# Sensors.net
KiCad netlist of a schematic drawn in Altium Designer
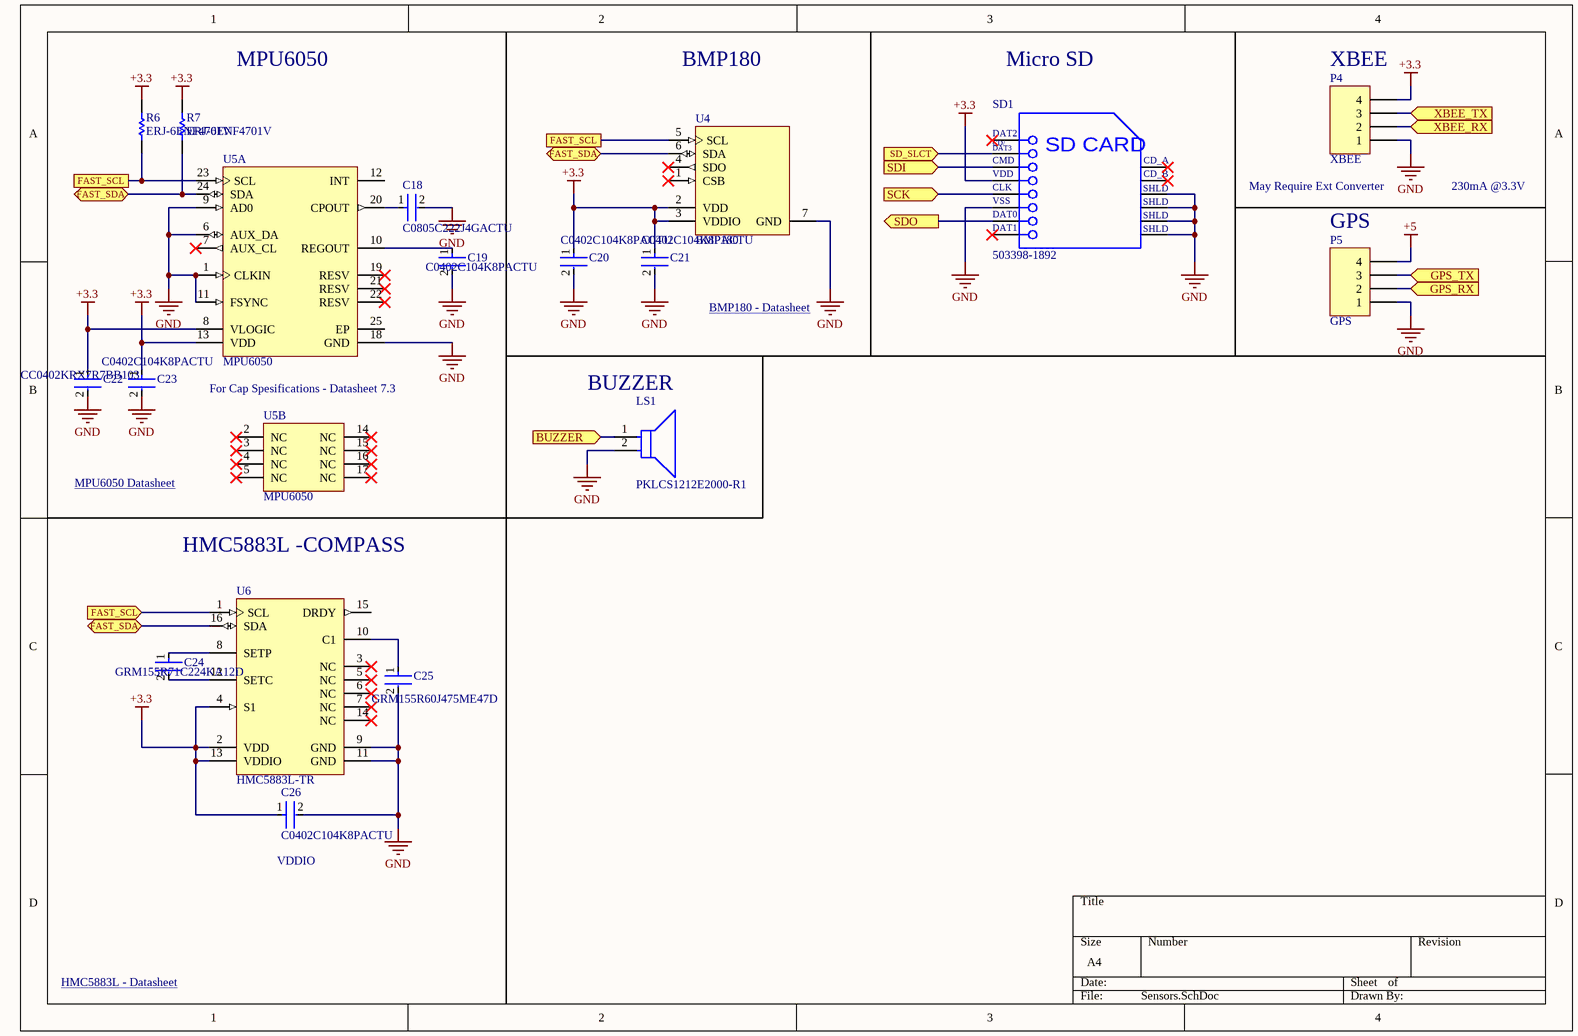
[diagram p0: Sensors.SchDoc]

(export (version "E")
  (design (tool "Eeschema 10.0.6"))
  (components
    (comp (ref "C18")
      (value "C0805C222J4GACTU")
      (footprint "FP-C0805C-DN-MFG")
      (description "Capacitor, Ceramic, 2.2Nf, 16Vdc, 5-% Tol, 5+% Tol, C0g-Tc Code, -30, 30Ppm-Tc Rohs Compliant: Yes")
      (fields
        (field (name "OCTOPART") "https://octopart.com/c0805c222j4gactu-kemet-17052493")
        (field (name "MANUFACTURER") "KEMET")
      )
      (libsource (lib "Altium Content Vault") (part "b4654b650e69147ec39a6b967a45e02"))
    )
    (comp (ref "C19")
      (value "C0402C104K8PACTU")
      (footprint "FP-C0402-BB-MFG")
      (description "CAP CER 0.1UF 10V X5R 0402")
      (fields (field (name "MANUFACTURER") "Kemet") (field (name "TOLERANCE") "0.1"))
      (libsource (lib "Altium Content Vault") (part "b4654b650e69147ec39a6b967a45e02"))
    )
    (comp (ref "C20")
      (value "C0402C104K8PACTU")
      (footprint "FP-C0402-BB-MFG")
      (description "CAP CER 0.1UF 10V X5R 0402")
      (fields (field (name "MANUFACTURER") "Kemet") (field (name "TOLERANCE") "0.1"))
      (libsource (lib "Altium Content Vault") (part "b4654b650e69147ec39a6b967a45e02"))
    )
    (comp (ref "C21")
      (value "C0402C104K8PACTU")
      (footprint "FP-C0402-BB-MFG")
      (description "CAP CER 0.1UF 10V X5R 0402")
      (fields (field (name "MANUFACTURER") "Kemet") (field (name "TOLERANCE") "0.1"))
      (libsource (lib "Altium Content Vault") (part "b4654b650e69147ec39a6b967a45e02"))
    )
    (comp (ref "C22")
      (value "CC0402KRX7R7BB103")
      (footprint "FP-CC0402-MFG")
      (description "CAP CER 10000PF 16V X7R 0402")
      (fields (field (name "TOLERANCE") "0.1") (field (name "MANUFACTURER") "YAGEO"))
      (libsource (lib "Altium Content Vault") (part "11868f565c42a9108669ba33697ecf6"))
    )
    (comp (ref "C23")
      (value "C0402C104K8PACTU")
      (footprint "FP-C0402-BB-MFG")
      (description "CAP CER 0.1UF 10V X5R 0402")
      (fields (field (name "MANUFACTURER") "Kemet") (field (name "TOLERANCE") "0.1"))
      (libsource (lib "Altium Content Vault") (part "b4654b650e69147ec39a6b967a45e02"))
    )
    (comp (ref "C24")
      (value "GRM155R71C224KA12D")
      (footprint "FP-GRM155-0_05-IPC_C")
      (description "Chip Multilayer Ceramic Capacitors for General Purpose, 0402, 0.22uF, X7R, 15%, 10%, 16V")
      (fields (field (name "VOLTAGE") "16V") (field (name "TOLERANCE") "10%"))
      (libsource (lib "Altium Content Vault") (part "02cd4be3c70576c341d710602a673aa"))
    )
    (comp (ref "C25")
      (value "GRM155R60J475ME47D")
      (footprint "FP-GRM155-0_1-IPC_B")
      (description "Chip Multilayer Ceramic Capacitors for General Purpose, 0402, 4.7uF, X5R, 15%, 20%, 6.3V")
      (fields (field (name "VOLTAGE") "6.3V") (field (name "TOLERANCE") "20%"))
      (libsource (lib "Altium Content Vault") (part "11868f565c42a9108669ba33697ecf6"))
    )
    (comp (ref "C26")
      (value "C0402C104K8PACTU")
      (footprint "FP-C0402-BB-MFG")
      (description "CAP CER 0.1UF 10V X5R 0402")
      (fields (field (name "MANUFACTURER") "Kemet") (field (name "TOLERANCE") "0.1"))
      (libsource (lib "Altium Content Vault") (part "b4654b650e69147ec39a6b967a45e02"))
    )
    (comp (ref "LS1")
      (value "PKLCS1212E2000-R1")
      (footprint "FP-PKLCS1212E2000-R1-MFG")
      (description "AUDIO PIEZO TRANSDUCER 12.5V SMD")
      (fields
        (field (name "MANUFACTURER") "Murata")
        (field (name "OCTOPART") "https://octopart.com/pklcs1212e2000-r1-murata-7123179")
      )
      (libsource (lib "Altium Content Vault") (part "5f581d31613f872430949aa526fd155"))
    )
    (comp (ref "P4")
      (value "XBEE")
      (footprint "HDR1X4")
      (description "Header, 4-Pin")
      (fields (field (name "PUBLISHER") "Altium Limited"))
      (libsource (lib "Miscellaneous Connectors") (part "Header 4"))
    )
    (comp (ref "P5")
      (value "GPS")
      (footprint "HDR1X4")
      (description "Header, 4-Pin")
      (fields (field (name "PUBLISHER") "Altium Limited"))
      (libsource (lib "Miscellaneous Connectors") (part "Header 4"))
    )
    (comp (ref "R6")
      (value "ERJ-6ENF4701V")
      (footprint "RESC2013X70X40NL20T20")
      (description "Chip Resistor, 4.7 KOhm, +/- 1%, 0.125 W, -55 to 155 degC, 0805 (2012 Metric), RoHS, Tape and Reel")
      (fields (field (name "MANUFACTURER") "Panasonic"))
      (libsource (lib "Altium Content Vault") (part "RES-2"))
    )
    (comp (ref "R7")
      (value "ERJ-6ENF4701V")
      (footprint "RESC2013X70X40NL20T20")
      (description "Chip Resistor, 4.7 KOhm, +/- 1%, 0.125 W, -55 to 155 degC, 0805 (2012 Metric), RoHS, Tape and Reel")
      (fields (field (name "MANUFACTURER") "Panasonic"))
      (libsource (lib "Altium Content Vault") (part "RES-2"))
    )
    (comp (ref "SD1")
      (value "503398-1892")
      (footprint "MOLX-503398-1892_V")
      (description "Micro SD Connector, Pitch 1.1 mm, 8 Position, Height 1.4 mm, -25 to 85 degC, RoHS, Tape and Reel")
      (fields (field (name "MANUFACTURER") "Molex"))
      (libsource (lib "Altium Content Vault") (part "CN-SD-8-2SW-4S"))
    )
    (comp (ref "U4")
      (value "BMP180")
      (footprint "BOSC-BMP180-7_V")
      (description "Digital Pressure Sensor, 1.8 to 3.6 V, -40 to 85 degC, 7-Pin LGA, RoHS")
      (fields (field (name "MANUFACTURER") "Bosch Sensortec"))
      (libsource (lib "Altium Content Vault") (part "BOSC-BMP180-7"))
    )
    (comp (ref "U5")
      (value "MPU6050")
      (footprint "INSE-QFN-24_V")
      (fields (field (name "TOLERANCE") "1%"))
      (libsource (lib "Altium Content Vault") (part "INSE-MPU6050-QFN-24"))
    )
    (comp (ref "U6")
      (value "HMC5883L-TR")
      (footprint "HONEY-LPCC-16_V")
      (description "Three-Axis Digital Compass IC, 2.16 to 3.6 V, -30 to 85 degC, 16-Pin PLCC, RoHS, Tape and Reel")
      (fields (field (name "MANUFACTURER") "Honeywell"))
      (libsource (lib "Altium Content Vault") (part "HONEY-HMC5883L-TR-LPCC-16"))
    )
  )
  (nets
    (net (code "1") (name "+3.3") (class "Default")
      (node (ref "C20") (pin "1") (pinfunction "1_1") (pintype "passive"))
      (node (ref "C21") (pin "1") (pinfunction "1_1") (pintype "passive"))
      (node (ref "C22") (pin "1") (pinfunction "1_1") (pintype "passive"))
      (node (ref "C23") (pin "1") (pinfunction "1_1") (pintype "passive"))
      (node (ref "C26") (pin "1") (pinfunction "1_1") (pintype "passive"))
      (node (ref "P4") (pin "4") (pinfunction "4_4") (pintype "passive"))
      (node (ref "R6") (pin "2") (pinfunction "2_2") (pintype "passive"))
      (node (ref "R7") (pin "2") (pinfunction "2_2") (pintype "passive"))
      (node (ref "SD1") (pin "4") (pinfunction "VDD_4") (pintype "passive"))
      (node (ref "U4") (pin "2") (pinfunction "VDD_2") (pintype "power_in"))
      (node (ref "U4") (pin "3") (pinfunction "VDDIO_3") (pintype "power_in"))
      (node (ref "U5") (pin "13") (pinfunction "VDD_13") (pintype "power_in"))
      (node (ref "U5") (pin "8") (pinfunction "VLOGIC_8") (pintype "power_in"))
      (node (ref "U6") (pin "13") (pinfunction "VDDIO_13") (pintype "power_in"))
      (node (ref "U6") (pin "2") (pinfunction "VDD_2") (pintype "power_in"))
      (node (ref "U6") (pin "4") (pinfunction "S1_4") (pintype "input"))
    )
    (net (code "2") (name "+5") (class "Default")
      (node (ref "P5") (pin "4") (pinfunction "4_4") (pintype "passive"))
    )
    (net (code "3") (name "/BUZZER") (class "Default")
      (node (ref "LS1") (pin "1") (pinfunction "1_1") (pintype "passive"))
    )
    (net (code "4") (name "/FAST_SCL") (class "Default")
      (node (ref "R6") (pin "1") (pinfunction "1_1") (pintype "passive"))
      (node (ref "U4") (pin "5") (pinfunction "SCL_5") (pintype "input"))
      (node (ref "U5") (pin "23") (pinfunction "SCL_23") (pintype "input"))
      (node (ref "U6") (pin "1") (pinfunction "SCL_1") (pintype "input"))
    )
    (net (code "5") (name "/FAST_SDA") (class "Default")
      (node (ref "R7") (pin "1") (pinfunction "1_1") (pintype "passive"))
      (node (ref "U4") (pin "6") (pinfunction "SDA_6") (pintype "bidirectional"))
      (node (ref "U5") (pin "24") (pinfunction "SDA_24") (pintype "bidirectional"))
      (node (ref "U6") (pin "16") (pinfunction "SDA_16") (pintype "bidirectional"))
    )
    (net (code "6") (name "/GPS_RX") (class "Default")
      (node (ref "P5") (pin "2") (pinfunction "2_2") (pintype "passive"))
    )
    (net (code "7") (name "/GPS_TX") (class "Default")
      (node (ref "P5") (pin "3") (pinfunction "3_3") (pintype "passive"))
    )
    (net (code "8") (name "/SCK") (class "Default")
      (node (ref "SD1") (pin "5") (pinfunction "CLK_5") (pintype "passive"))
    )
    (net (code "9") (name "/SDI") (class "Default")
      (node (ref "SD1") (pin "3") (pinfunction "CMD_3") (pintype "passive"))
    )
    (net (code "10") (name "/SDO") (class "Default")
      (node (ref "SD1") (pin "7") (pinfunction "DAT0_7") (pintype "passive"))
    )
    (net (code "11") (name "/SD_SLCT") (class "Default")
      (node (ref "SD1") (pin "2") (pinfunction "CD/DAT3_2") (pintype "passive"))
    )
    (net (code "12") (name "/XBEE_RX") (class "Default")
      (node (ref "P4") (pin "2") (pinfunction "2_2") (pintype "passive"))
    )
    (net (code "13") (name "/XBEE_TX") (class "Default")
      (node (ref "P4") (pin "3") (pinfunction "3_3") (pintype "passive"))
    )
    (net (code "14") (name "GND") (class "Default")
      (node (ref "C18") (pin "2") (pinfunction "2_2") (pintype "passive"))
      (node (ref "C19") (pin "2") (pinfunction "2_2") (pintype "passive"))
      (node (ref "C20") (pin "2") (pinfunction "2_2") (pintype "passive"))
      (node (ref "C21") (pin "2") (pinfunction "2_2") (pintype "passive"))
      (node (ref "C22") (pin "2") (pinfunction "2_2") (pintype "passive"))
      (node (ref "C23") (pin "2") (pinfunction "2_2") (pintype "passive"))
      (node (ref "C25") (pin "2") (pinfunction "2_2") (pintype "passive"))
      (node (ref "C26") (pin "2") (pinfunction "2_2") (pintype "passive"))
      (node (ref "LS1") (pin "2") (pinfunction "2_2") (pintype "passive"))
      (node (ref "P4") (pin "1") (pinfunction "1_1") (pintype "passive"))
      (node (ref "P5") (pin "1") (pinfunction "1_1") (pintype "passive"))
      (node (ref "SD1") (pin "11") (pinfunction "SHLD_11") (pintype "passive"))
      (node (ref "SD1") (pin "12") (pinfunction "SHLD_12") (pintype "passive"))
      (node (ref "SD1") (pin "13") (pinfunction "SHLD_13") (pintype "passive"))
      (node (ref "SD1") (pin "14") (pinfunction "SHLD_14") (pintype "passive"))
      (node (ref "SD1") (pin "6") (pinfunction "VSS_6") (pintype "passive"))
      (node (ref "U4") (pin "7") (pinfunction "GND_7") (pintype "power_in"))
      (node (ref "U5") (pin "1") (pinfunction "CLKIN_1") (pintype "input"))
      (node (ref "U5") (pin "11") (pinfunction "FSYNC_11") (pintype "input"))
      (node (ref "U5") (pin "18") (pinfunction "GND_18") (pintype "power_in"))
      (node (ref "U5") (pin "6") (pinfunction "AUX_DA_6") (pintype "bidirectional"))
      (node (ref "U5") (pin "9") (pinfunction "AD0_9") (pintype "input"))
      (node (ref "U6") (pin "11") (pinfunction "GND_11") (pintype "power_in"))
      (node (ref "U6") (pin "9") (pinfunction "GND_9") (pintype "power_in"))
    )
    (net (code "15") (name "Net-(U5A-CPOUT)") (class "Default")
      (node (ref "C18") (pin "1") (pinfunction "1_1") (pintype "passive"))
      (node (ref "U5") (pin "20") (pinfunction "CPOUT_20") (pintype "output"))
    )
    (net (code "16") (name "Net-(U5A-REGOUT)") (class "Default")
      (node (ref "C19") (pin "1") (pinfunction "1_1") (pintype "passive"))
      (node (ref "U5") (pin "10") (pinfunction "REGOUT_10") (pintype "passive"))
    )
    (net (code "17") (name "Net-(U6-C1)") (class "Default")
      (node (ref "C25") (pin "1") (pinfunction "1_1") (pintype "passive"))
      (node (ref "U6") (pin "10") (pinfunction "C1_10") (pintype "passive"))
    )
    (net (code "18") (name "Net-(U6-SETC)") (class "Default")
      (node (ref "C24") (pin "2") (pinfunction "2_2") (pintype "passive"))
      (node (ref "U6") (pin "12") (pinfunction "SETC_12") (pintype "passive"))
    )
    (net (code "19") (name "Net-(U6-SETP)") (class "Default")
      (node (ref "C24") (pin "1") (pinfunction "1_1") (pintype "passive"))
      (node (ref "U6") (pin "8") (pinfunction "SETP_8") (pintype "passive"))
    )
    (net (code "20") (name "unconnected-(SD1-CD_A-Pad9)") (class "Default")
      (node (ref "SD1") (pin "9") (pinfunction "CD_A_9") (pintype "passive+no_connect"))
    )
    (net (code "21") (name "unconnected-(SD1-CD_B-Pad10)") (class "Default")
      (node (ref "SD1") (pin "10") (pinfunction "CD_B_10") (pintype "passive+no_connect"))
    )
    (net (code "22") (name "unconnected-(SD1-DAT1-Pad8)") (class "Default")
      (node (ref "SD1") (pin "8") (pinfunction "DAT1_8") (pintype "passive+no_connect"))
    )
    (net (code "23") (name "unconnected-(SD1-DAT2-Pad1)") (class "Default")
      (node (ref "SD1") (pin "1") (pinfunction "DAT2_1") (pintype "passive+no_connect"))
    )
    (net (code "24") (name "unconnected-(U4-CSB-Pad1)") (class "Default")
      (node (ref "U4") (pin "1") (pinfunction "CSB_1") (pintype "input+no_connect"))
    )
    (net (code "25") (name "unconnected-(U4-SDO-Pad4)") (class "Default")
      (node (ref "U4") (pin "4") (pinfunction "SDO_4") (pintype "output+no_connect"))
    )
    (net (code "26") (name "unconnected-(U5A-AUX_CL-Pad7)") (class "Default")
      (node (ref "U5") (pin "7") (pinfunction "AUX_CL_7") (pintype "output+no_connect"))
    )
    (net (code "27") (name "unconnected-(U5A-EP-Pad25)") (class "Default")
      (node (ref "U5") (pin "25") (pinfunction "EP_25") (pintype "passive"))
    )
    (net (code "28") (name "unconnected-(U5A-INT-Pad12)") (class "Default")
      (node (ref "U5") (pin "12") (pinfunction "INT_12") (pintype "open_collector"))
    )
    (net (code "29") (name "unconnected-(U5A-RESV-Pad19)") (class "Default")
      (node (ref "U5") (pin "19") (pinfunction "RESV_19") (pintype "passive+no_connect"))
    )
    (net (code "30") (name "unconnected-(U5A-RESV-Pad21)") (class "Default")
      (node (ref "U5") (pin "21") (pinfunction "RESV_21") (pintype "passive+no_connect"))
    )
    (net (code "31") (name "unconnected-(U5A-RESV-Pad22)") (class "Default")
      (node (ref "U5") (pin "22") (pinfunction "RESV_22") (pintype "passive+no_connect"))
    )
    (net (code "32") (name "unconnected-(U5B-NC-Pad2)") (class "Default")
      (node (ref "U5") (pin "2") (pinfunction "NC_2") (pintype "passive+no_connect"))
    )
    (net (code "33") (name "unconnected-(U5B-NC-Pad3)") (class "Default")
      (node (ref "U5") (pin "3") (pinfunction "NC_3") (pintype "passive+no_connect"))
    )
    (net (code "34") (name "unconnected-(U5B-NC-Pad4)") (class "Default")
      (node (ref "U5") (pin "4") (pinfunction "NC_4") (pintype "passive+no_connect"))
    )
    (net (code "35") (name "unconnected-(U5B-NC-Pad5)") (class "Default")
      (node (ref "U5") (pin "5") (pinfunction "NC_5") (pintype "passive+no_connect"))
    )
    (net (code "36") (name "unconnected-(U5B-NC-Pad14)") (class "Default")
      (node (ref "U5") (pin "14") (pinfunction "NC_14") (pintype "passive+no_connect"))
    )
    (net (code "37") (name "unconnected-(U5B-NC-Pad15)") (class "Default")
      (node (ref "U5") (pin "15") (pinfunction "NC_15") (pintype "passive+no_connect"))
    )
    (net (code "38") (name "unconnected-(U5B-NC-Pad16)") (class "Default")
      (node (ref "U5") (pin "16") (pinfunction "NC_16") (pintype "passive+no_connect"))
    )
    (net (code "39") (name "unconnected-(U5B-NC-Pad17)") (class "Default")
      (node (ref "U5") (pin "17") (pinfunction "NC_17") (pintype "passive+no_connect"))
    )
    (net (code "40") (name "unconnected-(U6-DRDY-Pad15)") (class "Default")
      (node (ref "U6") (pin "15") (pinfunction "DRDY_15") (pintype "output"))
    )
    (net (code "41") (name "unconnected-(U6-NC-Pad3)") (class "Default")
      (node (ref "U6") (pin "3") (pinfunction "NC_3") (pintype "passive+no_connect"))
    )
    (net (code "42") (name "unconnected-(U6-NC-Pad5)") (class "Default")
      (node (ref "U6") (pin "5") (pinfunction "NC_5") (pintype "passive+no_connect"))
    )
    (net (code "43") (name "unconnected-(U6-NC-Pad6)") (class "Default")
      (node (ref "U6") (pin "6") (pinfunction "NC_6") (pintype "passive+no_connect"))
    )
    (net (code "44") (name "unconnected-(U6-NC-Pad7)") (class "Default")
      (node (ref "U6") (pin "7") (pinfunction "NC_7") (pintype "passive+no_connect"))
    )
    (net (code "45") (name "unconnected-(U6-NC-Pad14)") (class "Default")
      (node (ref "U6") (pin "14") (pinfunction "NC_14") (pintype "passive+no_connect"))
    )
  )
)
